# GSM.net
KiCad netlist of a schematic drawn in Altium Designer
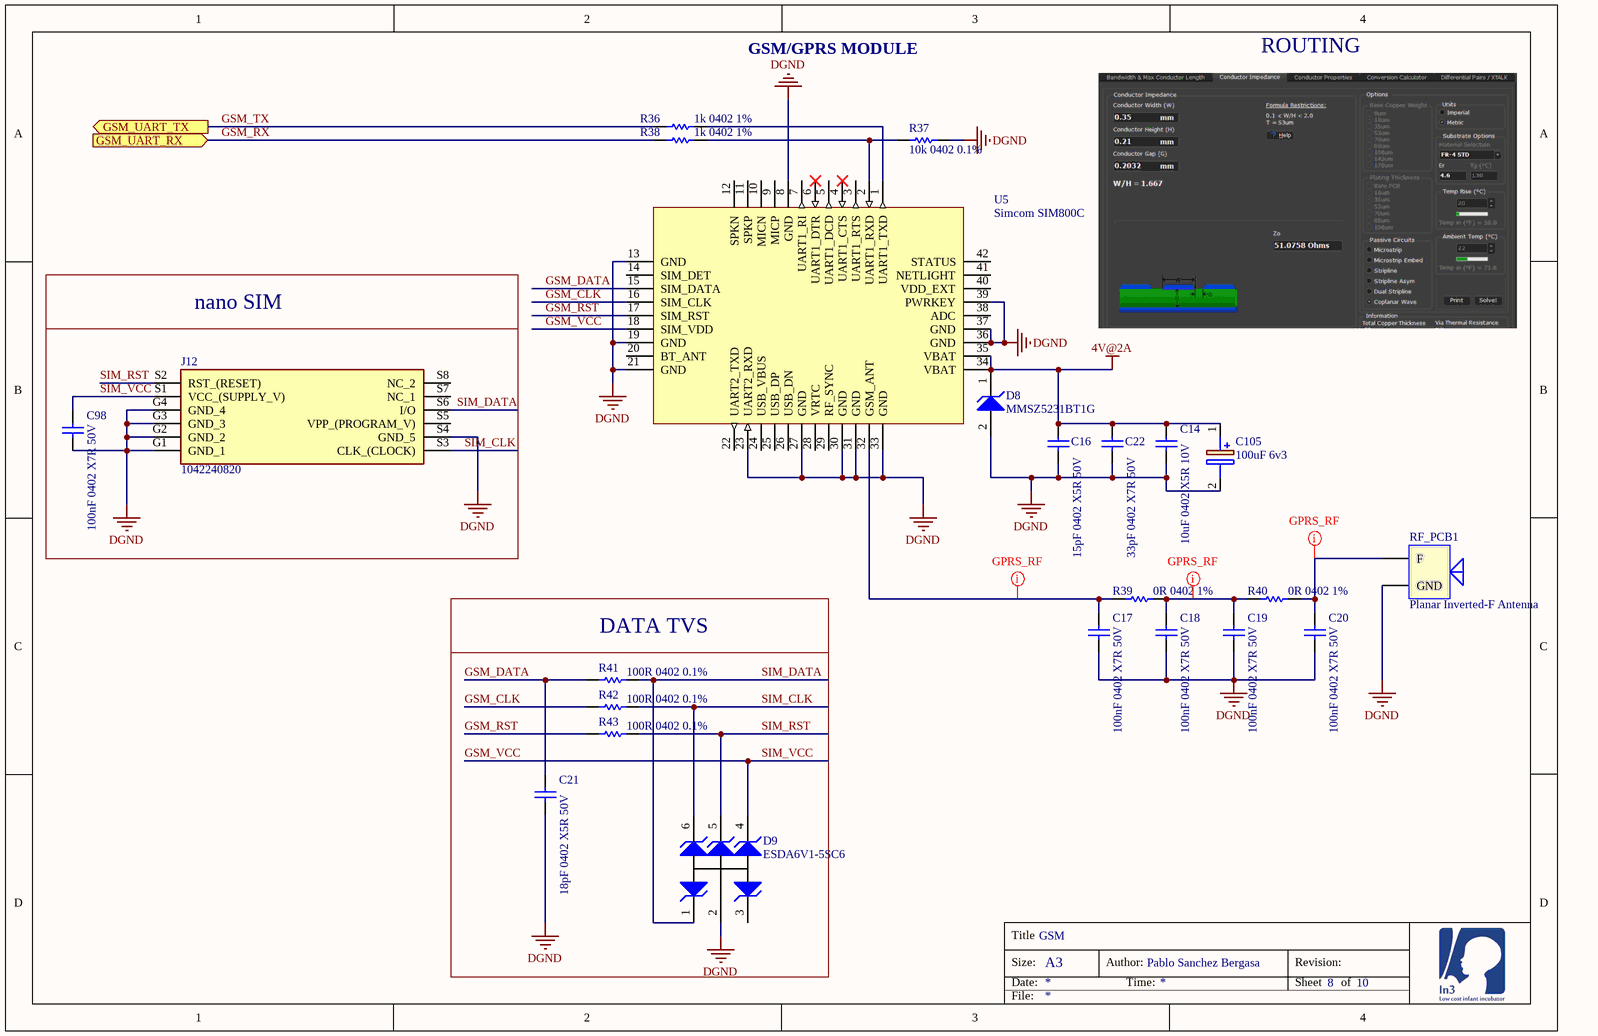
[diagram p0: GSM.SchDoc]

(export (version "E")
  (design (tool "Eeschema 10.0.6"))
  (components
    (comp (ref "C14")
      (value "10uF 0402 X5R 10V")
      (footprint "CAPC1005X55X25NL5T10")
      (libsource (lib "Altium Content Vault") (part "CAP-NP-2"))
    )
    (comp (ref "C16")
      (value "15pF 0402 X5R 50V")
      (footprint "CAPC1005X55X25NL5T10")
      (libsource (lib "Altium Content Vault") (part "CAP-NP-2"))
    )
    (comp (ref "C17")
      (value "100nF 0402 X7R 50V")
      (footprint "CAPC1005X55X25NL5T10")
      (libsource (lib "Altium Content Vault") (part "CAP-NP-2"))
    )
    (comp (ref "C18")
      (value "100nF 0402 X7R 50V")
      (footprint "CAPC1005X55X25NL5T10")
      (libsource (lib "Altium Content Vault") (part "CAP-NP-2"))
    )
    (comp (ref "C19")
      (value "100nF 0402 X7R 50V")
      (footprint "CAPC1005X55X25NL5T10")
      (libsource (lib "Altium Content Vault") (part "CAP-NP-2"))
    )
    (comp (ref "C20")
      (value "100nF 0402 X7R 50V")
      (footprint "CAPC1005X55X25NL5T10")
      (libsource (lib "Altium Content Vault") (part "CAP-NP-2"))
    )
    (comp (ref "C21")
      (value "18pF 0402 X5R 50V")
      (footprint "CAPC1005X55X25NL5T10")
      (libsource (lib "Altium Content Vault") (part "CAP-NP-2"))
    )
    (comp (ref "C22")
      (value "33pF 0402 X7R 50V")
      (footprint "CAPC1005X55X25NL5T10")
      (libsource (lib "Altium Content Vault") (part "CAP-NP-2"))
    )
    (comp (ref "C98")
      (value "100nF 0402 X7R 50V")
      (footprint "CAPC1005X55X25NL5T10")
      (libsource (lib "Altium Content Vault") (part "CAP-NP-2"))
    )
    (comp (ref "C105")
      (value "100uF 6v3")
      (footprint "SamacSys:CAPPM3216X180N")
      (description "Capacitor Polarised")
      (fields
        (field (name "MANUFACTURER_PART_NUMBER") "TMCMA0J107MTRF")
        (field (name "MOUSER PART NUMBER") "74-TMCMA0J107MTRF")
      )
      (libsource (lib "*") (part "TMCMA0J107MTRF"))
    )
    (comp (ref "D8")
      (value "MMSZ5231BT1G")
      (footprint "ONSC-SOD-123-2-425-04_V")
      (description "Zener Voltage Regulator, 500 mW, 2-Pin SOD-123, Pb-Free, Tape and Reel")
      (fields (field (name "MANUFACTURER") "On Semiconductor"))
      (libsource (lib "Altium Content Vault") (part "ONSC-K1A2-2"))
    )
    (comp (ref "D9")
      (value "ESDA6V1-5SC6")
      (footprint "MF06A_N")
      (description "ESDA Series 5 Channel 6.1 V 50 pF SMT Uni Directional Transil Array - SOT-23-6L")
      (fields (field (name "LCSC PART") "C6650"))
      (libsource (lib "in3ator_components") (part "CMP-924f5b40f9684d88-1"))
    )
    (comp (ref "J12")
      (value "1042240820")
      (footprint "SamacSys:1042240820")
      (description "Connector")
      (libsource (lib "*") (part "1042240820"))
    )
    (comp (ref "R36")
      (value "1k 0402 1%")
      (footprint "RESC1005X40X25ML05T10")
      (libsource (lib "Altium Content Vault") (part "RES"))
    )
    (comp (ref "R37")
      (value "10k 0402 0.1%")
      (footprint "RESC1005X40X25ML05T10")
      (libsource (lib "Altium Content Vault") (part "RES"))
    )
    (comp (ref "R38")
      (value "1k 0402 1%")
      (footprint "RESC1005X40X25ML05T10")
      (libsource (lib "Altium Content Vault") (part "RES"))
    )
    (comp (ref "R39")
      (value "0R 0402 1%")
      (footprint "RESC1005X40X25ML05T10")
      (libsource (lib "Altium Content Vault") (part "RES"))
    )
    (comp (ref "R40")
      (value "0R 0402 1%")
      (footprint "RESC1005X40X25ML05T10")
      (libsource (lib "Altium Content Vault") (part "RES"))
    )
    (comp (ref "R41")
      (value "100R 0402 0.1%")
      (footprint "RESC1005X40X25ML05T10")
      (libsource (lib "Altium Content Vault") (part "RES"))
    )
    (comp (ref "R42")
      (value "100R 0402 0.1%")
      (footprint "RESC1005X40X25ML05T10")
      (libsource (lib "Altium Content Vault") (part "RES"))
    )
    (comp (ref "R43")
      (value "100R 0402 0.1%")
      (footprint "RESC1005X40X25ML05T10")
      (libsource (lib "Altium Content Vault") (part "RES"))
    )
    (comp (ref "RF_PCB1")
      (value "Planar Inverted-F Antenna")
      (footprint "PCB-k9titb4465gfk1ijwrnj-1")
      (description "GSM900 and GSM1800  Frequency Bands PCB antenna")
      (libsource (lib "in3ator") (part "CMP-e704afk8c25r4a5ypw1c-12"))
    )
    (comp (ref "U5")
      (value "Simcom SIM800C")
      (footprint "SIM800C")
      (description "Module: GSM/Bluetooth; GPRS; 2G; 1800MHz, 900MHz; 85.6kbps; SMD")
      (fields (field (name "MANUFACTURER PART NUMBER") "SIM800C"))
      (libsource (lib "in3ator") (part "CMP-72dbb8ea0133ad1c-5"))
    )
  )
  (nets
    (net (code "1") (name "/GSM_CLK") (class "Default")
      (node (ref "R42") (pin "2") (pinfunction "2_2") (pintype "passive"))
      (node (ref "U5") (pin "16") (pinfunction "SIM_CLK_16") (pintype "passive"))
    )
    (net (code "2") (name "/GSM_DATA") (class "Default")
      (node (ref "C21") (pin "2") (pinfunction "2_2") (pintype "passive"))
      (node (ref "R41") (pin "2") (pinfunction "2_2") (pintype "passive"))
      (node (ref "U5") (pin "15") (pinfunction "SIM_DATA_15") (pintype "passive"))
    )
    (net (code "3") (name "/GSM_RST") (class "Default")
      (node (ref "R43") (pin "2") (pinfunction "2_2") (pintype "passive"))
      (node (ref "U5") (pin "17") (pinfunction "SIM_RST_17") (pintype "passive"))
    )
    (net (code "4") (name "/GSM_RX") (class "Default")
      (node (ref "R38") (pin "2") (pinfunction "2_2") (pintype "passive"))
    )
    (net (code "5") (name "/GSM_TX") (class "Default")
      (node (ref "R36") (pin "2") (pinfunction "2_2") (pintype "passive"))
    )
    (net (code "6") (name "/GSM_VCC") (class "Default")
      (node (ref "C98") (pin "2") (pinfunction "2_2") (pintype "passive"))
      (node (ref "D9") (pin "4") (pinfunction "A_4") (pintype "passive"))
      (node (ref "J12") (pin "S1") (pinfunction "VCC_(SUPPLY_V)_S1") (pintype "passive"))
      (node (ref "U5") (pin "18") (pinfunction "SIM_VDD_18") (pintype "passive"))
    )
    (net (code "7") (name "/SIM_CLK") (class "Default")
      (node (ref "D9") (pin "6") (pinfunction "A_6") (pintype "passive"))
      (node (ref "J12") (pin "S3") (pinfunction "CLK_(CLOCK)_S3") (pintype "passive"))
      (node (ref "R42") (pin "1") (pinfunction "1_1") (pintype "passive"))
    )
    (net (code "8") (name "/SIM_DATA") (class "Default")
      (node (ref "D9") (pin "1") (pinfunction "K_1") (pintype "passive"))
      (node (ref "J12") (pin "S6") (pinfunction "I/O_S6") (pintype "passive"))
      (node (ref "R41") (pin "1") (pinfunction "1_1") (pintype "passive"))
    )
    (net (code "9") (name "/SIM_RST") (class "Default")
      (node (ref "D9") (pin "5") (pinfunction "A_5") (pintype "passive"))
      (node (ref "J12") (pin "S2") (pinfunction "RST_(RESET)_S2") (pintype "passive"))
      (node (ref "R43") (pin "1") (pinfunction "1_1") (pintype "passive"))
    )
    (net (code "10") (name "4V@2A") (class "Default")
      (node (ref "C105") (pin "1") (pinfunction "+_1") (pintype "passive"))
      (node (ref "C14") (pin "2") (pinfunction "2_2") (pintype "passive"))
      (node (ref "C16") (pin "2") (pinfunction "2_2") (pintype "passive"))
      (node (ref "C22") (pin "1") (pinfunction "1_1") (pintype "passive"))
      (node (ref "D8") (pin "1") (pinfunction "K_1") (pintype "passive"))
      (node (ref "U5") (pin "34") (pinfunction "VBAT_34") (pintype "passive"))
      (node (ref "U5") (pin "35") (pinfunction "VBAT_35") (pintype "passive"))
    )
    (net (code "11") (name "DGND") (class "Default")
      (node (ref "C105") (pin "2") (pinfunction "-_2") (pintype "passive"))
      (node (ref "C14") (pin "1") (pinfunction "1_1") (pintype "passive"))
      (node (ref "C16") (pin "1") (pinfunction "1_1") (pintype "passive"))
      (node (ref "C17") (pin "1") (pinfunction "1_1") (pintype "passive"))
      (node (ref "C18") (pin "1") (pinfunction "1_1") (pintype "passive"))
      (node (ref "C19") (pin "1") (pinfunction "1_1") (pintype "passive"))
      (node (ref "C20") (pin "1") (pinfunction "1_1") (pintype "passive"))
      (node (ref "C21") (pin "1") (pinfunction "1_1") (pintype "passive"))
      (node (ref "C22") (pin "2") (pinfunction "2_2") (pintype "passive"))
      (node (ref "C98") (pin "1") (pinfunction "1_1") (pintype "passive"))
      (node (ref "D8") (pin "2") (pinfunction "A_2") (pintype "passive"))
      (node (ref "D9") (pin "2") (pinfunction "K_2") (pintype "passive"))
      (node (ref "J12") (pin "G1") (pinfunction "GND_1_G1") (pintype "passive"))
      (node (ref "J12") (pin "G2") (pinfunction "GND_2_G2") (pintype "passive"))
      (node (ref "J12") (pin "G3") (pinfunction "GND_3_G3") (pintype "passive"))
      (node (ref "J12") (pin "G4") (pinfunction "GND_4_G4") (pintype "passive"))
      (node (ref "J12") (pin "S4") (pinfunction "GND_5_S4") (pintype "passive"))
      (node (ref "R37") (pin "1") (pinfunction "1_1") (pintype "passive"))
      (node (ref "RF_PCB1") (pin "2") (pinfunction "GND_2") (pintype "passive"))
      (node (ref "U5") (pin "13") (pinfunction "GND_13") (pintype "passive"))
      (node (ref "U5") (pin "19") (pinfunction "GND_19") (pintype "passive"))
      (node (ref "U5") (pin "21") (pinfunction "GND_21") (pintype "passive"))
      (node (ref "U5") (pin "23") (pinfunction "UART2_RXD_23") (pintype "input"))
      (node (ref "U5") (pin "27") (pinfunction "GND_27") (pintype "power_in"))
      (node (ref "U5") (pin "30") (pinfunction "GND_30") (pintype "power_in"))
      (node (ref "U5") (pin "31") (pinfunction "GND_31") (pintype "power_in"))
      (node (ref "U5") (pin "33") (pinfunction "GND_33") (pintype "power_in"))
      (node (ref "U5") (pin "36") (pinfunction "GND_36") (pintype "power_in"))
      (node (ref "U5") (pin "37") (pinfunction "GND_37") (pintype "power_in"))
      (node (ref "U5") (pin "39") (pinfunction "PWRKEY_39") (pintype "passive"))
      (node (ref "U5") (pin "8") (pinfunction "GND_8") (pintype "power_in"))
    )
    (net (code "12") (name "Net-(C18-Pad2)") (class "Default")
      (node (ref "C18") (pin "2") (pinfunction "2_2") (pintype "passive"))
      (node (ref "C19") (pin "2") (pinfunction "2_2") (pintype "passive"))
      (node (ref "R39") (pin "1") (pinfunction "1_1") (pintype "passive"))
      (node (ref "R40") (pin "2") (pinfunction "2_2") (pintype "passive"))
    )
    (net (code "13") (name "Net-(RF_PCB1-F)") (class "Default")
      (node (ref "C20") (pin "2") (pinfunction "2_2") (pintype "passive"))
      (node (ref "R40") (pin "1") (pinfunction "1_1") (pintype "passive"))
      (node (ref "RF_PCB1") (pin "1") (pinfunction "F_1") (pintype "passive"))
    )
    (net (code "14") (name "Net-(U5-GSM_ANT)") (class "Default")
      (node (ref "C17") (pin "2") (pinfunction "2_2") (pintype "passive"))
      (node (ref "R39") (pin "2") (pinfunction "2_2") (pintype "passive"))
      (node (ref "U5") (pin "32") (pinfunction "GSM_ANT_32") (pintype "passive"))
    )
    (net (code "15") (name "Net-(U5-UART1_RXD)") (class "Default")
      (node (ref "R37") (pin "2") (pinfunction "2_2") (pintype "passive"))
      (node (ref "R38") (pin "1") (pinfunction "1_1") (pintype "passive"))
      (node (ref "U5") (pin "2") (pinfunction "UART1_RXD_2") (pintype "input"))
    )
    (net (code "16") (name "Net-(U5-UART1_TXD)") (class "Default")
      (node (ref "R36") (pin "1") (pinfunction "1_1") (pintype "passive"))
      (node (ref "U5") (pin "1") (pinfunction "UART1_TXD_1") (pintype "output"))
    )
    (net (code "17") (name "unconnected-(D9-K-Pad3)") (class "Default")
      (node (ref "D9") (pin "3") (pinfunction "K_3") (pintype "passive"))
    )
    (net (code "18") (name "unconnected-(J12-NC_1-PadS7)") (class "Default")
      (node (ref "J12") (pin "S7") (pinfunction "NC_1_S7") (pintype "passive"))
    )
    (net (code "19") (name "unconnected-(J12-NC_2-PadS8)") (class "Default")
      (node (ref "J12") (pin "S8") (pinfunction "NC_2_S8") (pintype "passive"))
    )
    (net (code "20") (name "unconnected-(J12-VPP_(PROGRAM_V)-PadS5)") (class "Default")
      (node (ref "J12") (pin "S5") (pinfunction "VPP_(PROGRAM_V)_S5") (pintype "passive"))
    )
    (net (code "21") (name "unconnected-(U5-ADC-Pad38)") (class "Default")
      (node (ref "U5") (pin "38") (pinfunction "ADC_38") (pintype "passive"))
    )
    (net (code "22") (name "unconnected-(U5-BT_ANT-Pad20)") (class "Default")
      (node (ref "U5") (pin "20") (pinfunction "BT_ANT_20") (pintype "passive"))
    )
    (net (code "23") (name "unconnected-(U5-MICN-Pad10)") (class "Default")
      (node (ref "U5") (pin "10") (pinfunction "MICN_10") (pintype "passive"))
    )
    (net (code "24") (name "unconnected-(U5-MICP-Pad9)") (class "Default")
      (node (ref "U5") (pin "9") (pinfunction "MICP_9") (pintype "passive"))
    )
    (net (code "25") (name "unconnected-(U5-NETLIGHT-Pad41)") (class "Default")
      (node (ref "U5") (pin "41") (pinfunction "NETLIGHT_41") (pintype "passive"))
    )
    (net (code "26") (name "unconnected-(U5-RF_SYNC-Pad29)") (class "Default")
      (node (ref "U5") (pin "29") (pinfunction "RF_SYNC_29") (pintype "passive"))
    )
    (net (code "27") (name "unconnected-(U5-SIM_DET-Pad14)") (class "Default")
      (node (ref "U5") (pin "14") (pinfunction "SIM_DET_14") (pintype "passive"))
    )
    (net (code "28") (name "unconnected-(U5-SPKN-Pad12)") (class "Default")
      (node (ref "U5") (pin "12") (pinfunction "SPKN_12") (pintype "passive"))
    )
    (net (code "29") (name "unconnected-(U5-SPKP-Pad11)") (class "Default")
      (node (ref "U5") (pin "11") (pinfunction "SPKP_11") (pintype "passive"))
    )
    (net (code "30") (name "unconnected-(U5-STATUS-Pad42)") (class "Default")
      (node (ref "U5") (pin "42") (pinfunction "STATUS_42") (pintype "passive"))
    )
    (net (code "31") (name "unconnected-(U5-UART1_CTS-Pad4)") (class "Default")
      (node (ref "U5") (pin "4") (pinfunction "UART1_CTS_4") (pintype "input+no_connect"))
    )
    (net (code "32") (name "unconnected-(U5-UART1_DCD-Pad5)") (class "Default")
      (node (ref "U5") (pin "5") (pinfunction "UART1_DCD_5") (pintype "output"))
    )
    (net (code "33") (name "unconnected-(U5-UART1_DTR-Pad6)") (class "Default")
      (node (ref "U5") (pin "6") (pinfunction "UART1_DTR_6") (pintype "input+no_connect"))
    )
    (net (code "34") (name "unconnected-(U5-UART1_RI-Pad7)") (class "Default")
      (node (ref "U5") (pin "7") (pinfunction "UART1_RI_7") (pintype "output"))
    )
    (net (code "35") (name "unconnected-(U5-UART1_RTS-Pad3)") (class "Default")
      (node (ref "U5") (pin "3") (pinfunction "UART1_RTS_3") (pintype "output"))
    )
    (net (code "36") (name "unconnected-(U5-UART2_TXD-Pad22)") (class "Default")
      (node (ref "U5") (pin "22") (pinfunction "UART2_TXD_22") (pintype "output"))
    )
    (net (code "37") (name "unconnected-(U5-USB_DN-Pad26)") (class "Default")
      (node (ref "U5") (pin "26") (pinfunction "USB_DN_26") (pintype "passive"))
    )
    (net (code "38") (name "unconnected-(U5-USB_DP-Pad25)") (class "Default")
      (node (ref "U5") (pin "25") (pinfunction "USB_DP_25") (pintype "passive"))
    )
    (net (code "39") (name "unconnected-(U5-USB_VBUS-Pad24)") (class "Default")
      (node (ref "U5") (pin "24") (pinfunction "USB_VBUS_24") (pintype "passive"))
    )
    (net (code "40") (name "unconnected-(U5-VDD_EXT-Pad40)") (class "Default")
      (node (ref "U5") (pin "40") (pinfunction "VDD_EXT_40") (pintype "passive"))
    )
    (net (code "41") (name "unconnected-(U5-VRTC-Pad28)") (class "Default")
      (node (ref "U5") (pin "28") (pinfunction "VRTC_28") (pintype "passive"))
    )
  )
)
